# dht21.net
KiCad netlist of a schematic drawn in EAGLE
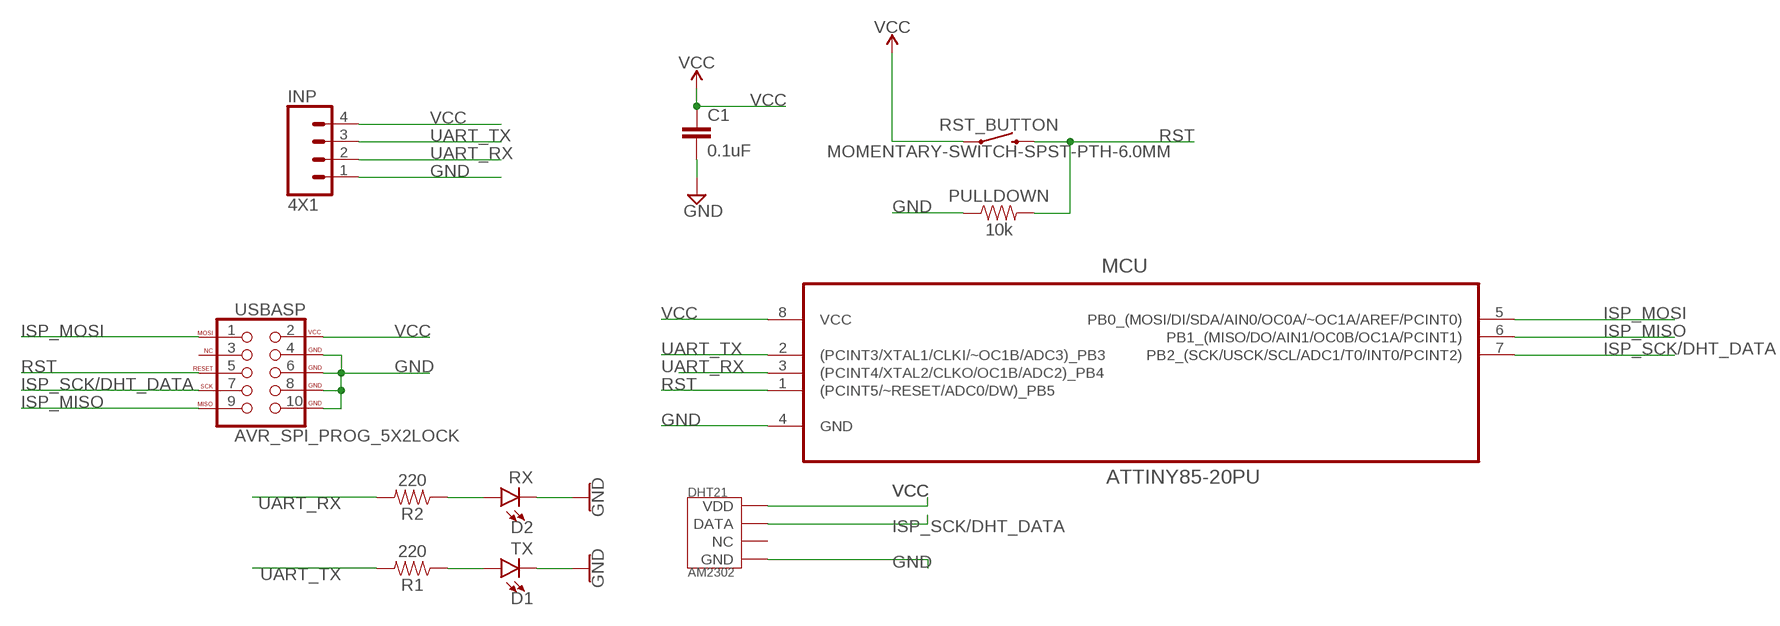
[diagram p0: schematic, sheet 1]

(export (version "E")
  (design (tool "Eeschema 10.0.6"))
  (components
    (comp (ref "C1")
      (value "0.1uF")
      (footprint "eagle-import:CAP-PTH-SMALL-KIT")
      (libsource (lib "eagle-import") (part "0.1UF-KIT-EZ-50V-20%"))
    )
    (comp (ref "D1")
      (value "TX")
      (footprint "eagle-import:LED_3MM")
      (libsource (lib "eagle-import") (part "LED3MM"))
    )
    (comp (ref "D2")
      (value "RX")
      (footprint "eagle-import:LED_3MM")
      (libsource (lib "eagle-import") (part "LED3MM"))
    )
    (comp (ref "DHT21")
      (value "AM2302")
      (footprint "eagle-import:SNR4-2.54-25.0X15.0X7.0MM")
      (libsource (lib "eagle-import") (part "TEM-HUM-AM2302(4P-25.0X15.0MM)"))
    )
    (comp (ref "INP")
      (value "4X1")
      (footprint "eagle-import:1X04")
      (libsource (lib "eagle-import") (part "CONN_04"))
    )
    (comp (ref "MCU")
      (value "ATTINY85-20PU")
      (footprint "eagle-import:DIP254P762X533-8")
      (libsource (lib "eagle-import") (part "ATTINY85-20PU"))
    )
    (comp (ref "PULLDOWN")
      (value "10k")
      (footprint "eagle-import:AXIAL-0.3")
      (libsource (lib "eagle-import") (part "10KOHM-HORIZ-1/4W-1%"))
    )
    (comp (ref "R1")
      (value "220")
      (footprint "eagle-import:AXIAL-0.3")
      (libsource (lib "eagle-import") (part "RESISTORAXIAL-0.3"))
    )
    (comp (ref "R2")
      (value "220")
      (footprint "eagle-import:AXIAL-0.3")
      (libsource (lib "eagle-import") (part "RESISTORAXIAL-0.3"))
    )
    (comp (ref "RST_BUTTON")
      (value "MOMENTARY-SWITCH-SPST-PTH-6.0MM")
      (footprint "eagle-import:TACTILE_SWITCH_PTH_6.0MM")
      (libsource (lib "eagle-import") (part "MOMENTARY-SWITCH-SPST-PTH-6.0MM"))
    )
    (comp (ref "USBASP")
      (value "AVR_SPI_PROG_5X2LOCK")
      (footprint "eagle-import:2X5-SHROUDED_LOCK")
      (libsource (lib "eagle-import") (part "AVR_SPI_PROG_5X2LOCK"))
    )
  )
  (nets
    (net (code "1") (name "/ISP_MISO") (class "Default")
      (node (ref "MCU") (pin "6") (pinfunction "PB1_(MISO/DO/AIN1/OC0B/OC1A/PCINT1)_6") (pintype "bidirectional"))
      (node (ref "USBASP") (pin "9") (pinfunction "MISO_9") (pintype "passive"))
    )
    (net (code "2") (name "/ISP_MOSI") (class "Default")
      (node (ref "MCU") (pin "5") (pinfunction "PB0_(MOSI/DI/SDA/AIN0/OC0A/~{OC1A/AREF/PCINT0})_5") (pintype "bidirectional"))
      (node (ref "USBASP") (pin "1") (pinfunction "MOSI_1") (pintype "passive"))
    )
    (net (code "3") (name "/ISP_SCK{slash}DHT_DATA") (class "Default")
      (node (ref "DHT21") (pin "P$2") (pinfunction "DATA_P$2") (pintype "bidirectional"))
      (node (ref "MCU") (pin "7") (pinfunction "PB2_(SCK/USCK/SCL/ADC1/T0/INT0/PCINT2)_7") (pintype "bidirectional"))
      (node (ref "USBASP") (pin "7") (pinfunction "SCK_7") (pintype "passive"))
    )
    (net (code "4") (name "/RST") (class "Default")
      (node (ref "MCU") (pin "1") (pinfunction "(PCINT5/~{RESET/ADC0/DW})_PB5_1") (pintype "bidirectional"))
      (node (ref "PULLDOWN") (pin "P$2") (pinfunction "2_P$2") (pintype "passive"))
      (node (ref "RST_BUTTON") (pin "3") (pinfunction "2_3") (pintype "passive"))
      (node (ref "USBASP") (pin "5") (pinfunction "RESET_5") (pintype "passive"))
    )
    (net (code "5") (name "/UART_RX") (class "Default")
      (node (ref "INP") (pin "2") (pinfunction "2_2") (pintype "passive"))
      (node (ref "MCU") (pin "3") (pinfunction "(PCINT4/XTAL2/CLKO/OC1B/ADC2)_PB4_3") (pintype "bidirectional"))
      (node (ref "R2") (pin "P$2") (pinfunction "2_P$2") (pintype "passive"))
    )
    (net (code "6") (name "/UART_TX") (class "Default")
      (node (ref "INP") (pin "3") (pinfunction "3_3") (pintype "passive"))
      (node (ref "MCU") (pin "2") (pinfunction "(PCINT3/XTAL1/CLKI/~{OC1B/ADC3})_PB3_2") (pintype "bidirectional"))
      (node (ref "R1") (pin "P$2") (pinfunction "2_P$2") (pintype "passive"))
    )
    (net (code "7") (name "GND") (class "Default")
      (node (ref "C1") (pin "2") (pinfunction "2_2") (pintype "passive"))
      (node (ref "D1") (pin "K") (pinfunction "C_K") (pintype "passive"))
      (node (ref "D2") (pin "K") (pinfunction "C_K") (pintype "passive"))
      (node (ref "DHT21") (pin "P$4") (pinfunction "GND_P$4") (pintype "power_in"))
      (node (ref "INP") (pin "1") (pinfunction "1_1") (pintype "passive"))
      (node (ref "MCU") (pin "4") (pinfunction "GND_4") (pintype "passive"))
      (node (ref "PULLDOWN") (pin "P$1") (pinfunction "1_P$1") (pintype "passive"))
      (node (ref "USBASP") (pin "10") (pinfunction "GND_10") (pintype "power_in"))
      (node (ref "USBASP") (pin "4") (pinfunction "GND_4") (pintype "power_in"))
      (node (ref "USBASP") (pin "6") (pinfunction "GND_6") (pintype "power_in"))
      (node (ref "USBASP") (pin "8") (pinfunction "GND_8") (pintype "power_in"))
    )
    (net (code "8") (name "Net-(R1-1)") (class "Default")
      (node (ref "D1") (pin "A") (pinfunction "A_A") (pintype "passive"))
      (node (ref "R1") (pin "P$1") (pinfunction "1_P$1") (pintype "passive"))
    )
    (net (code "9") (name "Net-(R2-1)") (class "Default")
      (node (ref "D2") (pin "A") (pinfunction "A_A") (pintype "passive"))
      (node (ref "R2") (pin "P$1") (pinfunction "1_P$1") (pintype "passive"))
    )
    (net (code "10") (name "VCC") (class "Default")
      (node (ref "C1") (pin "1") (pinfunction "1_1") (pintype "passive"))
      (node (ref "DHT21") (pin "P$1") (pinfunction "VDD_P$1") (pintype "power_in"))
      (node (ref "INP") (pin "4") (pinfunction "4_4") (pintype "passive"))
      (node (ref "MCU") (pin "8") (pinfunction "VCC_8") (pintype "power_in"))
      (node (ref "RST_BUTTON") (pin "1") (pinfunction "1_1") (pintype "passive"))
      (node (ref "USBASP") (pin "2") (pinfunction "VCC_2") (pintype "power_in"))
    )
    (net (code "11") (name "unconnected-(DHT21-NC-PadP$3)") (class "Default")
      (node (ref "DHT21") (pin "P$3") (pinfunction "NC_P$3") (pintype "no_connect"))
    )
    (net (code "12") (name "unconnected-(USBASP-NC-Pad3)") (class "Default")
      (node (ref "USBASP") (pin "3") (pinfunction "NC_3") (pintype "no_connect"))
    )
  )
)
